# rpi_board.net
KiCad netlist of a schematic drawn in EAGLE
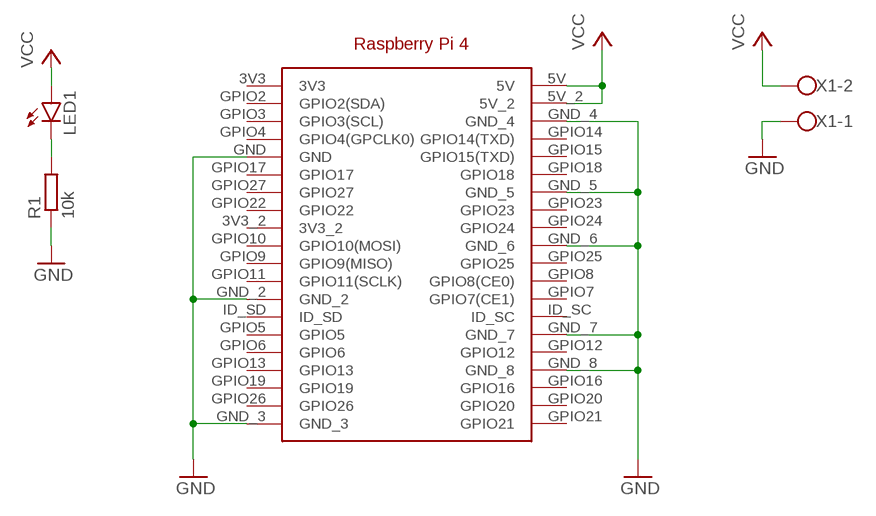
[diagram p0: schematic, sheet 1]

(export (version "E")
  (design (tool "Eeschema 10.0.6"))
  (components
    (comp (ref "LED1")
      (value "LEDSMT1206")
      (footprint "eagle-import:1206")
      (libsource (lib "eagle-import") (part "LEDSMT1206"))
    )
    (comp (ref "R1")
      (value "10k")
      (footprint "eagle-import:M1206")
      (libsource (lib "eagle-import") (part "R-EU_M1206"))
    )
    (comp (ref "U$1")
      (value "RPI_4")
      (footprint "eagle-import:RPI4_FOOTPRINT")
      (libsource (lib "eagle-import") (part "RPI_4"))
    )
    (comp (ref "X1")
      (value "W237-102")
      (footprint "eagle-import:W237-102")
      (fields (field (name "MPN") "237-102"))
      (libsource (lib "eagle-import") (part "W237-102"))
    )
  )
  (nets
    (net (code "1") (name "GND") (class "Default")
      (node (ref "R1") (pin "1") (pinfunction "1_1") (pintype "passive"))
      (node (ref "U$1") (pin "GND") (pinfunction "GND_GND") (pintype "bidirectional"))
      (node (ref "U$1") (pin "GND_2") (pinfunction "GND_2_GND_2") (pintype "bidirectional"))
      (node (ref "U$1") (pin "GND_3") (pinfunction "GND_3_GND_3") (pintype "bidirectional"))
      (node (ref "U$1") (pin "GND_4") (pinfunction "GND_4_GND_4") (pintype "bidirectional"))
      (node (ref "U$1") (pin "GND_5") (pinfunction "GND_5_GND_5") (pintype "bidirectional"))
      (node (ref "U$1") (pin "GND_6") (pinfunction "GND_6_GND_6") (pintype "bidirectional"))
      (node (ref "U$1") (pin "GND_7") (pinfunction "GND_7_GND_7") (pintype "bidirectional"))
      (node (ref "U$1") (pin "GND_8") (pinfunction "GND_8_GND_8") (pintype "bidirectional"))
      (node (ref "X1") (pin "1") (pinfunction "KL_1") (pintype "passive"))
    )
    (net (code "2") (name "Net-(LED1-PadC)") (class "Default")
      (node (ref "LED1") (pin "C") (pinfunction "C_C") (pintype "passive"))
      (node (ref "R1") (pin "2") (pinfunction "2_2") (pintype "passive"))
    )
    (net (code "3") (name "VCC") (class "Default")
      (node (ref "LED1") (pin "A") (pinfunction "A_A") (pintype "passive"))
      (node (ref "U$1") (pin "5V") (pinfunction "5V_5V") (pintype "bidirectional"))
      (node (ref "U$1") (pin "5V_2") (pinfunction "5V_2_5V_2") (pintype "bidirectional"))
      (node (ref "X1") (pin "2") (pinfunction "KL_2") (pintype "passive"))
    )
    (net (code "4") (name "unconnected-(U$1-GPIO2(SDA)-PadGPIO2)") (class "Default")
      (node (ref "U$1") (pin "GPIO2") (pinfunction "GPIO2(SDA)_GPIO2") (pintype "bidirectional"))
    )
    (net (code "5") (name "unconnected-(U$1-GPIO3(SCL)-PadGPIO3)") (class "Default")
      (node (ref "U$1") (pin "GPIO3") (pinfunction "GPIO3(SCL)_GPIO3") (pintype "bidirectional"))
    )
    (net (code "6") (name "unconnected-(U$1-GPIO4(GPCLK0)-PadGPIO4)") (class "Default")
      (node (ref "U$1") (pin "GPIO4") (pinfunction "GPIO4(GPCLK0)_GPIO4") (pintype "bidirectional"))
    )
    (net (code "7") (name "unconnected-(U$1-GPIO7(CE1)-PadGPIO7)") (class "Default")
      (node (ref "U$1") (pin "GPIO7") (pinfunction "GPIO7(CE1)_GPIO7") (pintype "bidirectional"))
    )
    (net (code "8") (name "unconnected-(U$1-GPIO8(CE0)-PadGPIO8)") (class "Default")
      (node (ref "U$1") (pin "GPIO8") (pinfunction "GPIO8(CE0)_GPIO8") (pintype "bidirectional"))
    )
    (net (code "9") (name "unconnected-(U$1-GPIO9(MISO)-PadGPIO9)") (class "Default")
      (node (ref "U$1") (pin "GPIO9") (pinfunction "GPIO9(MISO)_GPIO9") (pintype "bidirectional"))
    )
    (net (code "10") (name "unconnected-(U$1-GPIO10(MOSI)-PadGPIO10)") (class "Default")
      (node (ref "U$1") (pin "GPIO10") (pinfunction "GPIO10(MOSI)_GPIO10") (pintype "bidirectional"))
    )
    (net (code "11") (name "unconnected-(U$1-GPIO11(SCLK)-PadGPIO11)") (class "Default")
      (node (ref "U$1") (pin "GPIO11") (pinfunction "GPIO11(SCLK)_GPIO11") (pintype "bidirectional"))
    )
    (net (code "12") (name "unconnected-(U$1-GPIO14(TXD)-PadGPIO14)") (class "Default")
      (node (ref "U$1") (pin "GPIO14") (pinfunction "GPIO14(TXD)_GPIO14") (pintype "bidirectional"))
    )
    (net (code "13") (name "unconnected-(U$1-GPIO15(TXD)-PadGPIO15)") (class "Default")
      (node (ref "U$1") (pin "GPIO15") (pinfunction "GPIO15(TXD)_GPIO15") (pintype "bidirectional"))
    )
    (net (code "14") (name "unconnected-(U$1-Pad3V3)") (class "Default")
      (node (ref "U$1") (pin "3V3") (pinfunction "3V3_3V3") (pintype "bidirectional"))
    )
    (net (code "15") (name "unconnected-(U$1-Pad3V3_2)") (class "Default")
      (node (ref "U$1") (pin "3V3_2") (pinfunction "3V3_2_3V3_2") (pintype "bidirectional"))
    )
    (net (code "16") (name "unconnected-(U$1-PadGPIO5)") (class "Default")
      (node (ref "U$1") (pin "GPIO5") (pinfunction "GPIO5_GPIO5") (pintype "bidirectional"))
    )
    (net (code "17") (name "unconnected-(U$1-PadGPIO6)") (class "Default")
      (node (ref "U$1") (pin "GPIO6") (pinfunction "GPIO6_GPIO6") (pintype "bidirectional"))
    )
    (net (code "18") (name "unconnected-(U$1-PadGPIO12)") (class "Default")
      (node (ref "U$1") (pin "GPIO12") (pinfunction "GPIO12_GPIO12") (pintype "bidirectional"))
    )
    (net (code "19") (name "unconnected-(U$1-PadGPIO13)") (class "Default")
      (node (ref "U$1") (pin "GPIO13") (pinfunction "GPIO13_GPIO13") (pintype "bidirectional"))
    )
    (net (code "20") (name "unconnected-(U$1-PadGPIO16)") (class "Default")
      (node (ref "U$1") (pin "GPIO16") (pinfunction "GPIO16_GPIO16") (pintype "bidirectional"))
    )
    (net (code "21") (name "unconnected-(U$1-PadGPIO17)") (class "Default")
      (node (ref "U$1") (pin "GPIO17") (pinfunction "GPIO17_GPIO17") (pintype "bidirectional"))
    )
    (net (code "22") (name "unconnected-(U$1-PadGPIO18)") (class "Default")
      (node (ref "U$1") (pin "GPIO18") (pinfunction "GPIO18_GPIO18") (pintype "bidirectional"))
    )
    (net (code "23") (name "unconnected-(U$1-PadGPIO19)") (class "Default")
      (node (ref "U$1") (pin "GPIO19") (pinfunction "GPIO19_GPIO19") (pintype "bidirectional"))
    )
    (net (code "24") (name "unconnected-(U$1-PadGPIO20)") (class "Default")
      (node (ref "U$1") (pin "GPIO20") (pinfunction "GPIO20_GPIO20") (pintype "bidirectional"))
    )
    (net (code "25") (name "unconnected-(U$1-PadGPIO21)") (class "Default")
      (node (ref "U$1") (pin "GPIO21") (pinfunction "GPIO21_GPIO21") (pintype "bidirectional"))
    )
    (net (code "26") (name "unconnected-(U$1-PadGPIO22)") (class "Default")
      (node (ref "U$1") (pin "GPIO22") (pinfunction "GPIO22_GPIO22") (pintype "bidirectional"))
    )
    (net (code "27") (name "unconnected-(U$1-PadGPIO23)") (class "Default")
      (node (ref "U$1") (pin "GPIO23") (pinfunction "GPIO23_GPIO23") (pintype "bidirectional"))
    )
    (net (code "28") (name "unconnected-(U$1-PadGPIO24)") (class "Default")
      (node (ref "U$1") (pin "GPIO24") (pinfunction "GPIO24_GPIO24") (pintype "bidirectional"))
    )
    (net (code "29") (name "unconnected-(U$1-PadGPIO25)") (class "Default")
      (node (ref "U$1") (pin "GPIO25") (pinfunction "GPIO25_GPIO25") (pintype "bidirectional"))
    )
    (net (code "30") (name "unconnected-(U$1-PadGPIO26)") (class "Default")
      (node (ref "U$1") (pin "GPIO26") (pinfunction "GPIO26_GPIO26") (pintype "bidirectional"))
    )
    (net (code "31") (name "unconnected-(U$1-PadGPIO27)") (class "Default")
      (node (ref "U$1") (pin "GPIO27") (pinfunction "GPIO27_GPIO27") (pintype "bidirectional"))
    )
    (net (code "32") (name "unconnected-(U$1-PadID_SC)") (class "Default")
      (node (ref "U$1") (pin "ID_SC") (pinfunction "ID_SC_ID_SC") (pintype "bidirectional"))
    )
    (net (code "33") (name "unconnected-(U$1-PadID_SD)") (class "Default")
      (node (ref "U$1") (pin "ID_SD") (pinfunction "ID_SD_ID_SD") (pintype "bidirectional"))
    )
  )
)
